# Diff-Probe_Topsheet.net
KiCad netlist of a schematic drawn in Altium Designer
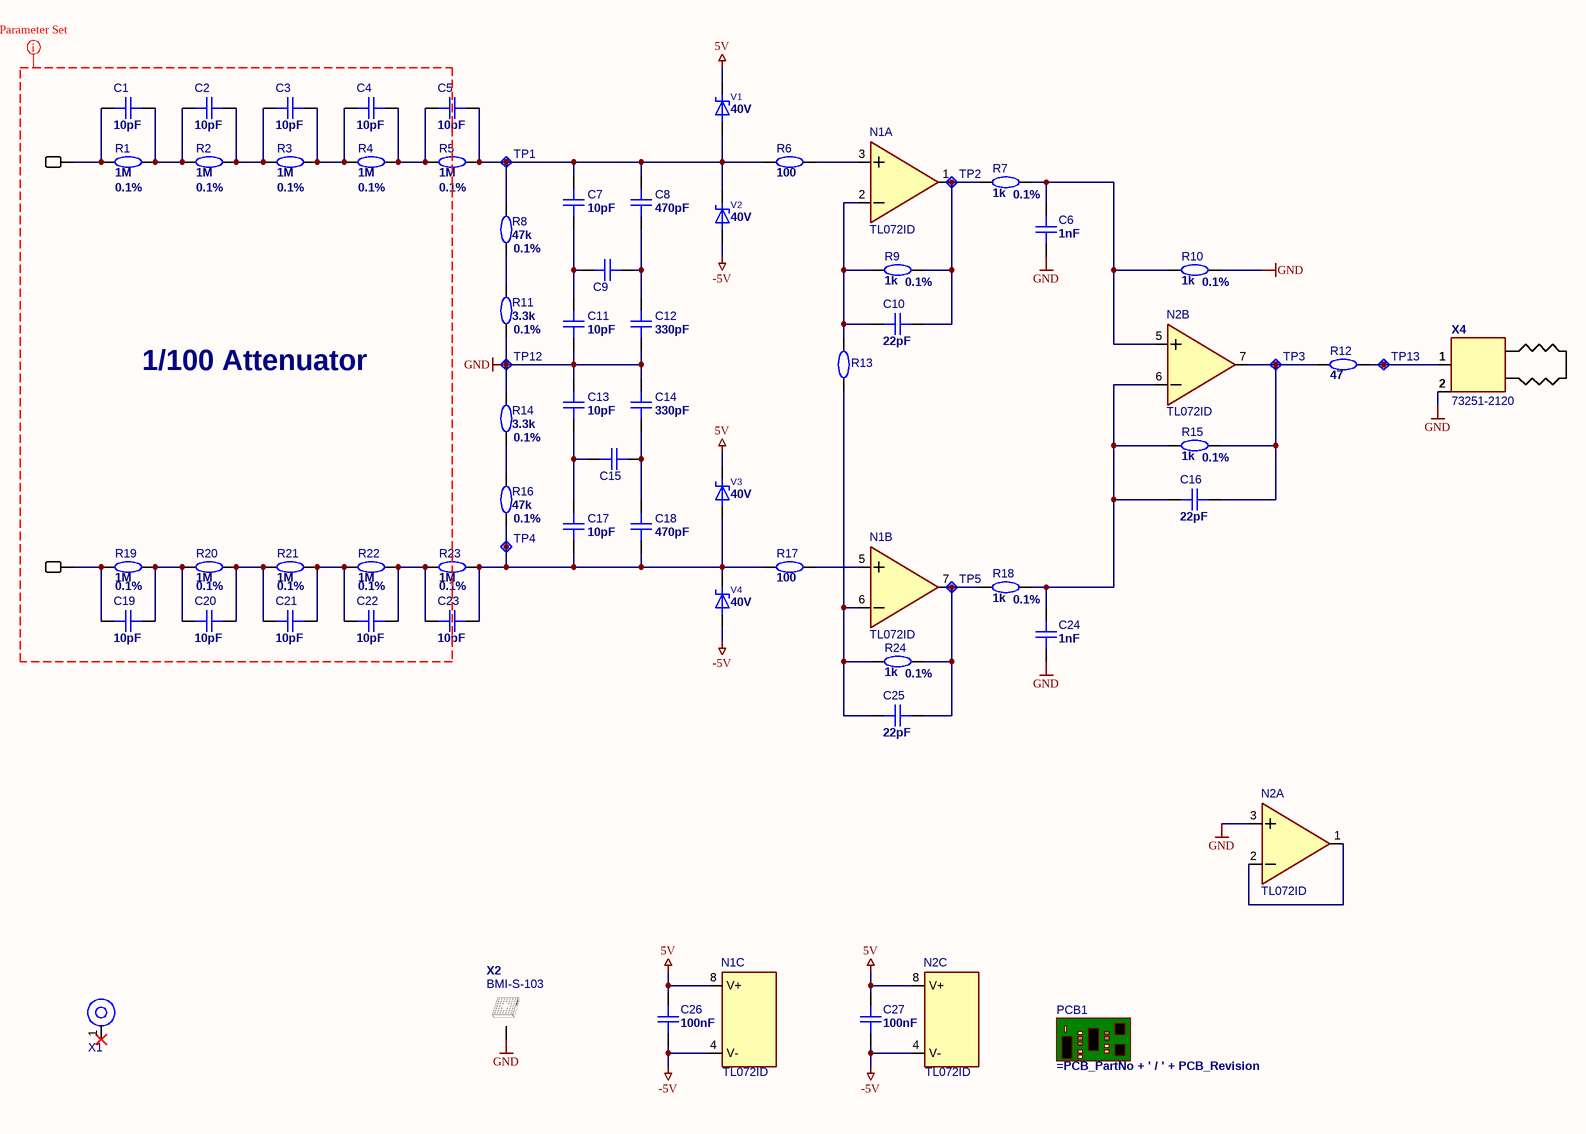
[diagram p0: Diff-Probe_Topsheet.SchDoc]

(export (version "E")
  (design (tool "Eeschema 10.0.6"))
  (components
    (comp (ref "C1")
      (value "10pF")
      (footprint "C-1206_3216_100_L_RF")
      (description "CAP CER 10PF 1KV U2J 1206")
      (fields
        (field (name "PART") "Cap Dummy")
        (field (name "Comment") "CAP 10PF 1KV U2J 1206")
        (field (name "USER") "zupa")
      )
      (libsource (lib "GPV Switzerland SA") (part "CAP"))
    )
    (comp (ref "C2")
      (value "10pF")
      (footprint "C-1206_3216_100_L_RF")
      (description "CAP CER 10PF 1KV U2J 1206")
      (fields
        (field (name "PART") "Cap Dummy")
        (field (name "Comment") "CAP 10PF 1KV U2J 1206")
        (field (name "USER") "zupa")
      )
      (libsource (lib "GPV Switzerland SA") (part "CAP"))
    )
    (comp (ref "C3")
      (value "10pF")
      (footprint "C-1206_3216_100_L_RF")
      (description "CAP CER 10PF 1KV U2J 1206")
      (fields
        (field (name "PART") "Cap Dummy")
        (field (name "Comment") "CAP 10PF 1KV U2J 1206")
        (field (name "USER") "zupa")
      )
      (libsource (lib "GPV Switzerland SA") (part "CAP"))
    )
    (comp (ref "C4")
      (value "10pF")
      (footprint "C-1206_3216_100_L_RF")
      (description "CAP CER 10PF 1KV U2J 1206")
      (fields
        (field (name "PART") "Cap Dummy")
        (field (name "Comment") "CAP 10PF 1KV U2J 1206")
        (field (name "USER") "zupa")
      )
      (libsource (lib "GPV Switzerland SA") (part "CAP"))
    )
    (comp (ref "C5")
      (value "10pF")
      (footprint "C-1206_3216_100_L_RF")
      (description "CAP CER 10PF 1KV U2J 1206")
      (fields
        (field (name "PART") "Cap Dummy")
        (field (name "Comment") "CAP 10PF 1KV U2J 1206")
        (field (name "USER") "zupa")
      )
      (libsource (lib "GPV Switzerland SA") (part "CAP"))
    )
    (comp (ref "C6")
      (value "1nF")
      (footprint "C-0603_1608_100_L_RF")
      (description "Cap Cer SMD 1n 50V 1% 0603 C0G")
      (fields
        (field (name "MANUFACTURER PART NUMBER") "06035A102FAT*")
        (field (name "MANUFACTURER") "AVX")
        (field (name "USER") "zupa")
      )
      (libsource (lib "GPV Switzerland SA") (part "CAP"))
    )
    (comp (ref "C7")
      (value "10pF")
      (footprint "C-0603_1608_095_L_RF")
      (description "Cap Cer SMD 10p 50V +/- 0.25pF  0603 C0G")
      (fields
        (field (name "MANUFACTURER") "AVX")
        (field (name "MANUFACTURER PART NUMBER") "06035A100CAT*")
        (field (name "USER") "zupa")
      )
      (libsource (lib "GPV Switzerland SA") (part "CAP"))
    )
    (comp (ref "C8")
      (value "470pF")
      (footprint "C-0603_1608_095_L_RF")
      (description "Cap Cer SMD 470p 100V 10% 0603 X7R")
      (fields
        (field (name "MANUFACTURER") "AVX")
        (field (name "MANUFACTURER PART NUMBER") "06031C471KAT2A")
        (field (name "USER") "zupa")
      )
      (libsource (lib "GPV Switzerland SA") (part "CAP"))
    )
    (comp (ref "C9")
      (value "Cap 0603")
      (footprint "C-0603_1608_095_L_RF")
      (description "Cap Cer SMD ?n ?V ?% 0603 ?")
      (fields (field (name "MANUFACTURER") "?") (field (name "USER") "zupa"))
      (libsource (lib "GPV Switzerland SA") (part "CAP"))
    )
    (comp (ref "C10")
      (value "22pF")
      (footprint "C-0603_1608_095_L_RF")
      (description "Cap Cer SMD 22p 50V 5% 0603 C0G")
      (fields
        (field (name "MANUFACTURER") "AVX")
        (field (name "MANUFACTURER PART NUMBER") "06035A220JAT")
        (field (name "USER") "zupa")
      )
      (libsource (lib "GPV Switzerland SA") (part "CAP"))
    )
    (comp (ref "C11")
      (value "10pF")
      (footprint "C-0603_1608_095_L_RF")
      (description "Cap Cer SMD 10p 50V +/- 0.25pF  0603 C0G")
      (fields
        (field (name "MANUFACTURER") "AVX")
        (field (name "MANUFACTURER PART NUMBER") "06035A100CAT*")
        (field (name "USER") "zupa")
      )
      (libsource (lib "GPV Switzerland SA") (part "CAP"))
    )
    (comp (ref "C12")
      (value "330pF")
      (footprint "C-0603_1608_095_L_RF")
      (description "Cap Cer SMD 330p 50V 2% 0603 C0G")
      (fields
        (field (name "MANUFACTURER") "MURATA")
        (field (name "MANUFACTURER PART NUMBER") "GRM1885C1H331GA01D")
        (field (name "USER") "zupa")
      )
      (libsource (lib "GPV Switzerland SA") (part "CAP"))
    )
    (comp (ref "C13")
      (value "10pF")
      (footprint "C-0603_1608_095_L_RF")
      (description "Cap Cer SMD 10p 50V +/- 0.25pF  0603 C0G")
      (fields
        (field (name "MANUFACTURER") "AVX")
        (field (name "MANUFACTURER PART NUMBER") "06035A100CAT*")
        (field (name "USER") "zupa")
      )
      (libsource (lib "GPV Switzerland SA") (part "CAP"))
    )
    (comp (ref "C14")
      (value "330pF")
      (footprint "C-0603_1608_095_L_RF")
      (description "Cap Cer SMD 330p 50V 2% 0603 C0G")
      (fields
        (field (name "MANUFACTURER") "MURATA")
        (field (name "MANUFACTURER PART NUMBER") "GRM1885C1H331GA01D")
        (field (name "USER") "zupa")
      )
      (libsource (lib "GPV Switzerland SA") (part "CAP"))
    )
    (comp (ref "C15")
      (value "Cap 0603")
      (footprint "C-0603_1608_095_L_RF")
      (description "Cap Cer SMD ?n ?V ?% 0603 ?")
      (fields (field (name "MANUFACTURER") "?") (field (name "USER") "zupa"))
      (libsource (lib "GPV Switzerland SA") (part "CAP"))
    )
    (comp (ref "C16")
      (value "22pF")
      (footprint "C-0603_1608_095_L_RF")
      (description "Cap Cer SMD 22p 50V 5% 0603 C0G")
      (fields
        (field (name "MANUFACTURER") "AVX")
        (field (name "MANUFACTURER PART NUMBER") "06035A220JAT")
        (field (name "USER") "zupa")
      )
      (libsource (lib "GPV Switzerland SA") (part "CAP"))
    )
    (comp (ref "C17")
      (value "10pF")
      (footprint "C-0603_1608_095_L_RF")
      (description "Cap Cer SMD 10p 50V +/- 0.25pF  0603 C0G")
      (fields
        (field (name "MANUFACTURER") "AVX")
        (field (name "MANUFACTURER PART NUMBER") "06035A100CAT*")
        (field (name "USER") "zupa")
      )
      (libsource (lib "GPV Switzerland SA") (part "CAP"))
    )
    (comp (ref "C18")
      (value "470pF")
      (footprint "C-0603_1608_095_L_RF")
      (description "Cap Cer SMD 470p 100V 10% 0603 X7R")
      (fields
        (field (name "MANUFACTURER") "AVX")
        (field (name "MANUFACTURER PART NUMBER") "06031C471KAT2A")
        (field (name "USER") "zupa")
      )
      (libsource (lib "GPV Switzerland SA") (part "CAP"))
    )
    (comp (ref "C19")
      (value "10pF")
      (footprint "C-1206_3216_100_L_RF")
      (description "CAP CER 10PF 1KV U2J 1206")
      (fields
        (field (name "PART") "Cap Dummy")
        (field (name "Comment") "CAP 10PF 1KV U2J 1206")
        (field (name "USER") "zupa")
      )
      (libsource (lib "GPV Switzerland SA") (part "CAP"))
    )
    (comp (ref "C20")
      (value "10pF")
      (footprint "C-1206_3216_100_L_RF")
      (description "CAP CER 10PF 1KV U2J 1206")
      (fields
        (field (name "PART") "Cap Dummy")
        (field (name "Comment") "CAP 10PF 1KV U2J 1206")
        (field (name "USER") "zupa")
      )
      (libsource (lib "GPV Switzerland SA") (part "CAP"))
    )
    (comp (ref "C21")
      (value "10pF")
      (footprint "C-1206_3216_100_L_RF")
      (description "CAP CER 10PF 1KV U2J 1206")
      (fields
        (field (name "PART") "Cap Dummy")
        (field (name "Comment") "CAP 10PF 1KV U2J 1206")
        (field (name "USER") "zupa")
      )
      (libsource (lib "GPV Switzerland SA") (part "CAP"))
    )
    (comp (ref "C22")
      (value "10pF")
      (footprint "C-1206_3216_100_L_RF")
      (description "CAP CER 10PF 1KV U2J 1206")
      (fields
        (field (name "PART") "Cap Dummy")
        (field (name "Comment") "CAP 10PF 1KV U2J 1206")
        (field (name "USER") "zupa")
      )
      (libsource (lib "GPV Switzerland SA") (part "CAP"))
    )
    (comp (ref "C23")
      (value "10pF")
      (footprint "C-1206_3216_100_L_RF")
      (description "CAP CER 10PF 1KV U2J 1206")
      (fields
        (field (name "PART") "Cap Dummy")
        (field (name "Comment") "CAP 10PF 1KV U2J 1206")
        (field (name "USER") "zupa")
      )
      (libsource (lib "GPV Switzerland SA") (part "CAP"))
    )
    (comp (ref "C24")
      (value "1nF")
      (footprint "C-0603_1608_100_L_RF")
      (description "Cap Cer SMD 1n 50V 1% 0603 C0G")
      (fields
        (field (name "MANUFACTURER PART NUMBER") "06035A102FAT*")
        (field (name "MANUFACTURER") "AVX")
        (field (name "USER") "zupa")
      )
      (libsource (lib "GPV Switzerland SA") (part "CAP"))
    )
    (comp (ref "C25")
      (value "22pF")
      (footprint "C-0603_1608_095_L_RF")
      (description "Cap Cer SMD 22p 50V 5% 0603 C0G")
      (fields
        (field (name "MANUFACTURER") "AVX")
        (field (name "MANUFACTURER PART NUMBER") "06035A220JAT")
        (field (name "USER") "zupa")
      )
      (libsource (lib "GPV Switzerland SA") (part "CAP"))
    )
    (comp (ref "C26")
      (value "100nF")
      (footprint "C-0603_1608_095_L_RF")
      (description "Cap Cer SMD 100n 100V 10% 0603 X7R")
      (fields
        (field (name "MANUFACTURER PART NUMBER") "GRM188R72A104KA35")
        (field (name "MANUFACTURER") "MURATA")
        (field (name "USER") "zupa")
      )
      (libsource (lib "GPV Switzerland SA") (part "CAP"))
    )
    (comp (ref "C27")
      (value "100nF")
      (footprint "C-0603_1608_095_L_RF")
      (description "Cap Cer SMD 100n 100V 10% 0603 X7R")
      (fields
        (field (name "MANUFACTURER PART NUMBER") "GRM188R72A104KA35")
        (field (name "MANUFACTURER") "MURATA")
        (field (name "USER") "zupa")
      )
      (libsource (lib "GPV Switzerland SA") (part "CAP"))
    )
    (comp (ref "N1")
      (value "TL072ID")
      (footprint "SO8_L_RF")
      (description "IC OPAMP JFET 3MHZ 8SOIC")
      (fields
        (field (name "MANUFACTURER") "Texas Instruments")
        (field (name "MANUFACTURER PART NUMBER") "TL072IDR")
        (field (name "USER") "zupa")
      )
      (libsource (lib "GPV Switzerland SA") (part "TL072ID"))
    )
    (comp (ref "N2")
      (value "TL072ID")
      (footprint "SO8_L_RF")
      (description "IC OPAMP JFET 3MHZ 8SOIC")
      (fields
        (field (name "MANUFACTURER") "Texas Instruments")
        (field (name "MANUFACTURER PART NUMBER") "TL072IDR")
        (field (name "USER") "zupa")
      )
      (libsource (lib "GPV Switzerland SA") (part "TL072ID"))
    )
    (comp (ref "PCB1")
      (value "/")
      (footprint "Dummy_PCB-Parameter_SM")
      (description "<PCB DesignName Revision>")
      (fields (field (name "Comment") "PCB_Dummy") (field (name "USER") "balu"))
      (libsource (lib "GPV Switzerland SA") (part "PCB"))
    )
    (comp (ref "R1")
      (value "1M")
      (footprint "R-1206_3216_065_L_RF")
      (description "Res SMD 1M 1% 0.25W 1206")
      (fields
        (field (name "MANUFACTURER PART NUMBER") "RC1206FR-071ML")
        (field (name "MANUFACTURER") "YAGEO")
        (field (name "USER") "zupa")
      )
      (libsource (lib "GPV Switzerland SA") (part "RES"))
    )
    (comp (ref "R2")
      (value "1M")
      (footprint "R-1206_3216_065_L_RF")
      (description "Res SMD 1M 1% 0.25W 1206")
      (fields
        (field (name "MANUFACTURER PART NUMBER") "RC1206FR-071ML")
        (field (name "MANUFACTURER") "YAGEO")
        (field (name "USER") "zupa")
      )
      (libsource (lib "GPV Switzerland SA") (part "RES"))
    )
    (comp (ref "R3")
      (value "1M")
      (footprint "R-1206_3216_065_L_RF")
      (description "Res SMD 1M 1% 0.25W 1206")
      (fields
        (field (name "MANUFACTURER PART NUMBER") "RC1206FR-071ML")
        (field (name "MANUFACTURER") "YAGEO")
        (field (name "USER") "zupa")
      )
      (libsource (lib "GPV Switzerland SA") (part "RES"))
    )
    (comp (ref "R4")
      (value "1M")
      (footprint "R-1206_3216_065_L_RF")
      (description "Res SMD 1M 1% 0.25W 1206")
      (fields
        (field (name "MANUFACTURER PART NUMBER") "RC1206FR-071ML")
        (field (name "MANUFACTURER") "YAGEO")
        (field (name "USER") "zupa")
      )
      (libsource (lib "GPV Switzerland SA") (part "RES"))
    )
    (comp (ref "R5")
      (value "1M")
      (footprint "R-1206_3216_065_L_RF")
      (description "Res SMD 1M 1% 0.25W 1206")
      (fields
        (field (name "MANUFACTURER PART NUMBER") "RC1206FR-071ML")
        (field (name "MANUFACTURER") "YAGEO")
        (field (name "USER") "zupa")
      )
      (libsource (lib "GPV Switzerland SA") (part "RES"))
    )
    (comp (ref "R6")
      (value "100")
      (footprint "R-0603_1608_050_L_RF")
      (description "Res SMD 100R 1% 0.1W 0603")
      (fields
        (field (name "MANUFACTURER") "YAGEO")
        (field (name "MANUFACTURER PART NUMBER") "RC0603FR-07100RL")
        (field (name "USER") "zupa")
      )
      (libsource (lib "GPV Switzerland SA") (part "RES"))
    )
    (comp (ref "R7")
      (value "1k")
      (footprint "R-0603_1608_050_L_RF")
      (description "Res SMD 1k 1% 0.1W 0603")
      (fields
        (field (name "MANUFACTURER") "YAGEO")
        (field (name "MANUFACTURER PART NUMBER") "RC0603FR-071KL")
        (field (name "USER") "zupa")
      )
      (libsource (lib "GPV Switzerland SA") (part "RES"))
    )
    (comp (ref "R8")
      (value "47k")
      (footprint "R-0603_1608_050_L_RF")
      (description "Res SMD 47k 1% 0.1W 0603")
      (fields
        (field (name "MANUFACTURER PART NUMBER") "RC0603FR-0747KL")
        (field (name "MANUFACTURER") "YAGEO")
        (field (name "USER") "zupa")
      )
      (libsource (lib "GPV Switzerland SA") (part "RES"))
    )
    (comp (ref "R9")
      (value "1k")
      (footprint "R-0603_1608_050_L_RF")
      (description "Res SMD 1k 1% 0.1W 0603")
      (fields
        (field (name "MANUFACTURER") "YAGEO")
        (field (name "MANUFACTURER PART NUMBER") "RC0603FR-071KL")
        (field (name "USER") "zupa")
      )
      (libsource (lib "GPV Switzerland SA") (part "RES"))
    )
    (comp (ref "R10")
      (value "1k")
      (footprint "R-0603_1608_050_L_RF")
      (description "Res SMD 1k 1% 0.1W 0603")
      (fields
        (field (name "MANUFACTURER") "YAGEO")
        (field (name "MANUFACTURER PART NUMBER") "RC0603FR-071KL")
        (field (name "USER") "zupa")
      )
      (libsource (lib "GPV Switzerland SA") (part "RES"))
    )
    (comp (ref "R11")
      (value "3.3k")
      (footprint "R-0603_1608_050_L_RF")
      (description "Res SMD 3k3 1% 0.1W 0603")
      (fields
        (field (name "MANUFACTURER") "YAGEO")
        (field (name "MANUFACTURER PART NUMBER") "RT0603FRE073K3L")
        (field (name "USER") "napa")
      )
      (libsource (lib "GPV Switzerland SA") (part "RES"))
    )
    (comp (ref "R12")
      (value "47")
      (footprint "R-0603_1608_050_L_RF")
      (description "Res SMD 47R 1% 0.1W 0603")
      (fields
        (field (name "MANUFACTURER PART NUMBER") "RC0603FR-0747RL")
        (field (name "MANUFACTURER") "YAGEO")
        (field (name "USER") "zupa")
      )
      (libsource (lib "GPV Switzerland SA") (part "RES"))
    )
    (comp (ref "R13")
      (value "Res 0603")
      (footprint "R-0603_1608_050_L_RF")
      (description "Res SMD ?R? ?% 0.1W 0603")
      (fields (field (name "MANUFACTURER") "?") (field (name "USER") "zupa"))
      (libsource (lib "GPV Switzerland SA") (part "RES"))
    )
    (comp (ref "R14")
      (value "3.3k")
      (footprint "R-0603_1608_050_L_RF")
      (description "Res SMD 3k3 1% 0.1W 0603")
      (fields
        (field (name "MANUFACTURER") "YAGEO")
        (field (name "MANUFACTURER PART NUMBER") "RT0603FRE073K3L")
        (field (name "USER") "napa")
      )
      (libsource (lib "GPV Switzerland SA") (part "RES"))
    )
    (comp (ref "R15")
      (value "1k")
      (footprint "R-0603_1608_050_L_RF")
      (description "Res SMD 1k 1% 0.1W 0603")
      (fields
        (field (name "MANUFACTURER") "YAGEO")
        (field (name "MANUFACTURER PART NUMBER") "RC0603FR-071KL")
        (field (name "USER") "zupa")
      )
      (libsource (lib "GPV Switzerland SA") (part "RES"))
    )
    (comp (ref "R16")
      (value "47k")
      (footprint "R-0603_1608_050_L_RF")
      (description "Res SMD 47k 1% 0.1W 0603")
      (fields
        (field (name "MANUFACTURER PART NUMBER") "RC0603FR-0747KL")
        (field (name "MANUFACTURER") "YAGEO")
        (field (name "USER") "zupa")
      )
      (libsource (lib "GPV Switzerland SA") (part "RES"))
    )
    (comp (ref "R17")
      (value "100")
      (footprint "R-0603_1608_050_L_RF")
      (description "Res SMD 100R 1% 0.1W 0603")
      (fields
        (field (name "MANUFACTURER") "YAGEO")
        (field (name "MANUFACTURER PART NUMBER") "RC0603FR-07100RL")
        (field (name "USER") "zupa")
      )
      (libsource (lib "GPV Switzerland SA") (part "RES"))
    )
    (comp (ref "R18")
      (value "1k")
      (footprint "R-0603_1608_050_L_RF")
      (description "Res SMD 1k 1% 0.1W 0603")
      (fields
        (field (name "MANUFACTURER") "YAGEO")
        (field (name "MANUFACTURER PART NUMBER") "RC0603FR-071KL")
        (field (name "USER") "zupa")
      )
      (libsource (lib "GPV Switzerland SA") (part "RES"))
    )
    (comp (ref "R19")
      (value "1M")
      (footprint "R-1206_3216_065_L_RF")
      (description "Res SMD 1M 1% 0.25W 1206")
      (fields
        (field (name "MANUFACTURER PART NUMBER") "RC1206FR-071ML")
        (field (name "MANUFACTURER") "YAGEO")
        (field (name "USER") "zupa")
      )
      (libsource (lib "GPV Switzerland SA") (part "RES"))
    )
    (comp (ref "R20")
      (value "1M")
      (footprint "R-1206_3216_065_L_RF")
      (description "Res SMD 1M 1% 0.25W 1206")
      (fields
        (field (name "MANUFACTURER PART NUMBER") "RC1206FR-071ML")
        (field (name "MANUFACTURER") "YAGEO")
        (field (name "USER") "zupa")
      )
      (libsource (lib "GPV Switzerland SA") (part "RES"))
    )
    (comp (ref "R21")
      (value "1M")
      (footprint "R-1206_3216_065_L_RF")
      (description "Res SMD 1M 1% 0.25W 1206")
      (fields
        (field (name "MANUFACTURER PART NUMBER") "RC1206FR-071ML")
        (field (name "MANUFACTURER") "YAGEO")
        (field (name "USER") "zupa")
      )
      (libsource (lib "GPV Switzerland SA") (part "RES"))
    )
    (comp (ref "R22")
      (value "1M")
      (footprint "R-1206_3216_065_L_RF")
      (description "Res SMD 1M 1% 0.25W 1206")
      (fields
        (field (name "MANUFACTURER PART NUMBER") "RC1206FR-071ML")
        (field (name "MANUFACTURER") "YAGEO")
        (field (name "USER") "zupa")
      )
      (libsource (lib "GPV Switzerland SA") (part "RES"))
    )
    (comp (ref "R23")
      (value "1M")
      (footprint "R-1206_3216_065_L_RF")
      (description "Res SMD 1M 1% 0.25W 1206")
      (fields
        (field (name "MANUFACTURER PART NUMBER") "RC1206FR-071ML")
        (field (name "MANUFACTURER") "YAGEO")
        (field (name "USER") "zupa")
      )
      (libsource (lib "GPV Switzerland SA") (part "RES"))
    )
    (comp (ref "R24")
      (value "1k")
      (footprint "R-0603_1608_050_L_RF")
      (description "Res SMD 1k 1% 0.1W 0603")
      (fields
        (field (name "MANUFACTURER") "YAGEO")
        (field (name "MANUFACTURER PART NUMBER") "RC0603FR-071KL")
        (field (name "USER") "zupa")
      )
      (libsource (lib "GPV Switzerland SA") (part "RES"))
    )
    (comp (ref "R30")
      (value "~")
      (footprint "Lötpad_2x3")
      (description "Solderpad 2mm x 3mm")
      (libsource (lib "Global Library") (part "Lötpad_2mmx3mm"))
    )
    (comp (ref "R31")
      (value "~")
      (footprint "Lötpad_2x3")
      (description "Solderpad 2mm x 3mm")
      (libsource (lib "Global Library") (part "Lötpad_2mmx3mm"))
    )
    (comp (ref "TP1")
      (value "TestPoint 1.6mm with via")
      (footprint "TP_1.6mm_via")
      (description "TestPoint 1.6mm with via v70h30")
      (fields (field (name "USER") "epph"))
      (libsource (lib "GPV Switzerland SA") (part "Testpoint"))
    )
    (comp (ref "TP2")
      (value "TestPoint 1.6mm with via")
      (footprint "TP_1.6mm_via")
      (description "TestPoint 1.6mm with via v70h30")
      (fields (field (name "USER") "epph"))
      (libsource (lib "GPV Switzerland SA") (part "Testpoint"))
    )
    (comp (ref "TP3")
      (value "TestPoint 1.6mm with via")
      (footprint "TP_1.6mm_via")
      (description "TestPoint 1.6mm with via v70h30")
      (fields (field (name "USER") "epph"))
      (libsource (lib "GPV Switzerland SA") (part "Testpoint"))
    )
    (comp (ref "TP4")
      (value "TestPoint 1.6mm with via")
      (footprint "TP_1.6mm_via")
      (description "TestPoint 1.6mm with via v70h30")
      (fields (field (name "USER") "epph"))
      (libsource (lib "GPV Switzerland SA") (part "Testpoint"))
    )
    (comp (ref "TP5")
      (value "TestPoint 1.6mm with via")
      (footprint "TP_1.6mm_via")
      (description "TestPoint 1.6mm with via v70h30")
      (fields (field (name "USER") "epph"))
      (libsource (lib "GPV Switzerland SA") (part "Testpoint"))
    )
    (comp (ref "TP12")
      (value "TestPoint 1.6mm with via")
      (footprint "TP_1.6mm_via")
      (description "TestPoint 1.6mm with via v70h30")
      (fields (field (name "USER") "epph"))
      (libsource (lib "GPV Switzerland SA") (part "Testpoint"))
    )
    (comp (ref "TP13")
      (value "TestPoint 1.6mm with via")
      (footprint "TP_1.6mm_via")
      (description "TestPoint 1.6mm with via v70h30")
      (fields (field (name "USER") "epph"))
      (libsource (lib "GPV Switzerland SA") (part "Testpoint"))
    )
    (comp (ref "V1")
      (value "40V")
      (footprint "SMA_DO214AC_L_RF")
      (description "Diode Schottky 40V 1A SMA")
      (fields
        (field (name "MANUFACTURER") "VISHAY")
        (field (name "MANUFACTURER PART NUMBER") "SS14-E3")
        (field (name "USER") "epph")
      )
      (libsource (lib "GPV Switzerland SA") (part "SCHOTTKY"))
    )
    (comp (ref "V2")
      (value "40V")
      (footprint "SMA_DO214AC_L_RF")
      (description "Diode Schottky 40V 1A SMA")
      (fields
        (field (name "MANUFACTURER") "VISHAY")
        (field (name "MANUFACTURER PART NUMBER") "SS14-E3")
        (field (name "USER") "epph")
      )
      (libsource (lib "GPV Switzerland SA") (part "SCHOTTKY"))
    )
    (comp (ref "V3")
      (value "40V")
      (footprint "SMA_DO214AC_L_RF")
      (description "Diode Schottky 40V 1A SMA")
      (fields
        (field (name "MANUFACTURER") "VISHAY")
        (field (name "MANUFACTURER PART NUMBER") "SS14-E3")
        (field (name "USER") "epph")
      )
      (libsource (lib "GPV Switzerland SA") (part "SCHOTTKY"))
    )
    (comp (ref "V4")
      (value "40V")
      (footprint "SMA_DO214AC_L_RF")
      (description "Diode Schottky 40V 1A SMA")
      (fields
        (field (name "MANUFACTURER") "VISHAY")
        (field (name "MANUFACTURER PART NUMBER") "SS14-E3")
        (field (name "USER") "epph")
      )
      (libsource (lib "GPV Switzerland SA") (part "SCHOTTKY"))
    )
    (comp (ref "X1")
      (value "AnschlussPad_D3.2_P6mm")
      (footprint "A-MountingHole-0600x0600_0320")
      (description "Anschlusspad mit 6mm Pad und 3.2mm Drill")
      (libsource (lib "GPV Switzerland SA") (part "Anschluss-Pad"))
    )
    (comp (ref "X2")
      (value "BMI-S-103")
      (footprint "BMI-S-103")
      (description "EMI Shield 26.2mm x 26.2mm, soldered")
      (fields
        (field (name "MANUFACTURER") "Laird")
        (field (name "PART_VALIDATED") "Yes ¦ No")
        (field (name "FOOTPRINT_VALIDATED") "Yes ¦ No")
      )
      (libsource (lib "Global Library") (part "BMI-S-103"))
    )
    (comp (ref "X4")
      (value "73251-2120")
      (footprint "73251-2120")
      (description "CONN RF SMA")
      (fields (field (name "MANUFACTURER") "MOLEX"))
      (libsource (lib "Global Library") (part "73251-2120"))
    )
  )
  (nets
    (net (code "1") (name "-5V") (class "Default")
      (node (ref "C26") (pin "1") (pinfunction "1_1") (pintype "passive"))
      (node (ref "C27") (pin "1") (pinfunction "1_1") (pintype "passive"))
      (node (ref "N1") (pin "4") (pinfunction "V-_4") (pintype "power_in"))
      (node (ref "N2") (pin "4") (pinfunction "V-_4") (pintype "power_in"))
      (node (ref "V2") (pin "1") (pinfunction "1_1") (pintype "passive"))
      (node (ref "V4") (pin "1") (pinfunction "1_1") (pintype "passive"))
    )
    (net (code "2") (name "5V") (class "Default")
      (node (ref "C26") (pin "2") (pinfunction "2_2") (pintype "passive"))
      (node (ref "C27") (pin "2") (pinfunction "2_2") (pintype "passive"))
      (node (ref "N1") (pin "8") (pinfunction "V+_8") (pintype "power_in"))
      (node (ref "N2") (pin "8") (pinfunction "V+_8") (pintype "power_in"))
      (node (ref "V1") (pin "2") (pinfunction "2_2") (pintype "passive"))
      (node (ref "V3") (pin "2") (pinfunction "2_2") (pintype "passive"))
    )
    (net (code "3") (name "GND") (class "Default")
      (node (ref "C11") (pin "1") (pinfunction "1_1") (pintype "passive"))
      (node (ref "C12") (pin "1") (pinfunction "1_1") (pintype "passive"))
      (node (ref "C13") (pin "2") (pinfunction "2_2") (pintype "passive"))
      (node (ref "C14") (pin "2") (pinfunction "2_2") (pintype "passive"))
      (node (ref "C24") (pin "1") (pinfunction "1_1") (pintype "passive"))
      (node (ref "C6") (pin "1") (pinfunction "1_1") (pintype "passive"))
      (node (ref "N2") (pin "3") (pintype "passive"))
      (node (ref "R10") (pin "2") (pinfunction "2_2") (pintype "passive"))
      (node (ref "R11") (pin "1") (pinfunction "1_1") (pintype "passive"))
      (node (ref "R14") (pin "2") (pinfunction "2_2") (pintype "passive"))
      (node (ref "TP12") (pin "1") (pinfunction "1_1") (pintype "passive"))
      (node (ref "X2") (pin "S") (pintype "passive"))
      (node (ref "X4") (pin "2") (pintype "passive"))
    )
    (net (code "4") (name "Net-(C1-Pad1)") (class "Default")
      (node (ref "C1") (pin "1") (pinfunction "1_1") (pintype "passive"))
      (node (ref "R1") (pin "1") (pinfunction "1_1") (pintype "passive"))
      (node (ref "R30") (pin "1") (pintype "passive"))
    )
    (net (code "5") (name "Net-(C1-Pad2)") (class "Default")
      (node (ref "C1") (pin "2") (pinfunction "2_2") (pintype "passive"))
      (node (ref "C2") (pin "1") (pinfunction "1_1") (pintype "passive"))
      (node (ref "R1") (pin "2") (pinfunction "2_2") (pintype "passive"))
      (node (ref "R2") (pin "1") (pinfunction "1_1") (pintype "passive"))
    )
    (net (code "6") (name "Net-(C2-Pad2)") (class "Default")
      (node (ref "C2") (pin "2") (pinfunction "2_2") (pintype "passive"))
      (node (ref "C3") (pin "1") (pinfunction "1_1") (pintype "passive"))
      (node (ref "R2") (pin "2") (pinfunction "2_2") (pintype "passive"))
      (node (ref "R3") (pin "1") (pinfunction "1_1") (pintype "passive"))
    )
    (net (code "7") (name "Net-(C3-Pad2)") (class "Default")
      (node (ref "C3") (pin "2") (pinfunction "2_2") (pintype "passive"))
      (node (ref "C4") (pin "1") (pinfunction "1_1") (pintype "passive"))
      (node (ref "R3") (pin "2") (pinfunction "2_2") (pintype "passive"))
      (node (ref "R4") (pin "1") (pinfunction "1_1") (pintype "passive"))
    )
    (net (code "8") (name "Net-(C4-Pad2)") (class "Default")
      (node (ref "C4") (pin "2") (pinfunction "2_2") (pintype "passive"))
      (node (ref "C5") (pin "1") (pinfunction "1_1") (pintype "passive"))
      (node (ref "R4") (pin "2") (pinfunction "2_2") (pintype "passive"))
      (node (ref "R5") (pin "1") (pinfunction "1_1") (pintype "passive"))
    )
    (net (code "9") (name "Net-(C5-Pad2)") (class "Default")
      (node (ref "C5") (pin "2") (pinfunction "2_2") (pintype "passive"))
      (node (ref "C7") (pin "2") (pinfunction "2_2") (pintype "passive"))
      (node (ref "C8") (pin "2") (pinfunction "2_2") (pintype "passive"))
      (node (ref "R5") (pin "2") (pinfunction "2_2") (pintype "passive"))
      (node (ref "R6") (pin "1") (pinfunction "1_1") (pintype "passive"))
      (node (ref "R8") (pin "2") (pinfunction "2_2") (pintype "passive"))
      (node (ref "TP1") (pin "1") (pinfunction "1_1") (pintype "passive"))
      (node (ref "V1") (pin "1") (pinfunction "1_1") (pintype "passive"))
      (node (ref "V2") (pin "2") (pinfunction "2_2") (pintype "passive"))
    )
    (net (code "10") (name "Net-(C6-Pad2)") (class "Default")
      (node (ref "C6") (pin "2") (pinfunction "2_2") (pintype "passive"))
      (node (ref "N2") (pin "5") (pintype "passive"))
      (node (ref "R10") (pin "1") (pinfunction "1_1") (pintype "passive"))
      (node (ref "R7") (pin "2") (pinfunction "2_2") (pintype "passive"))
    )
    (net (code "11") (name "Net-(C10-Pad1)") (class "Default")
      (node (ref "C10") (pin "1") (pinfunction "1_1") (pintype "passive"))
      (node (ref "N1") (pin "2") (pintype "passive"))
      (node (ref "R13") (pin "2") (pinfunction "2_2") (pintype "passive"))
      (node (ref "R9") (pin "1") (pinfunction "1_1") (pintype "passive"))
    )
    (net (code "12") (name "Net-(C10-Pad2)") (class "Default")
      (node (ref "C10") (pin "2") (pinfunction "2_2") (pintype "passive"))
      (node (ref "N1") (pin "1") (pintype "passive"))
      (node (ref "R7") (pin "1") (pinfunction "1_1") (pintype "passive"))
      (node (ref "R9") (pin "2") (pinfunction "2_2") (pintype "passive"))
      (node (ref "TP2") (pin "1") (pinfunction "1_1") (pintype "passive"))
    )
    (net (code "13") (name "Net-(C11-Pad2)") (class "Default")
      (node (ref "C11") (pin "2") (pinfunction "2_2") (pintype "passive"))
      (node (ref "C7") (pin "1") (pinfunction "1_1") (pintype "passive"))
      (node (ref "C9") (pin "2") (pinfunction "2_2") (pintype "passive"))
    )
    (net (code "14") (name "Net-(C12-Pad2)") (class "Default")
      (node (ref "C12") (pin "2") (pinfunction "2_2") (pintype "passive"))
      (node (ref "C8") (pin "1") (pinfunction "1_1") (pintype "passive"))
      (node (ref "C9") (pin "1") (pinfunction "1_1") (pintype "passive"))
    )
    (net (code "15") (name "Net-(C13-Pad1)") (class "Default")
      (node (ref "C13") (pin "1") (pinfunction "1_1") (pintype "passive"))
      (node (ref "C15") (pin "2") (pinfunction "2_2") (pintype "passive"))
      (node (ref "C17") (pin "2") (pinfunction "2_2") (pintype "passive"))
    )
    (net (code "16") (name "Net-(C14-Pad1)") (class "Default")
      (node (ref "C14") (pin "1") (pinfunction "1_1") (pintype "passive"))
      (node (ref "C15") (pin "1") (pinfunction "1_1") (pintype "passive"))
      (node (ref "C18") (pin "2") (pinfunction "2_2") (pintype "passive"))
    )
    (net (code "17") (name "Net-(C16-Pad1)") (class "Default")
      (node (ref "C16") (pin "1") (pinfunction "1_1") (pintype "passive"))
      (node (ref "C24") (pin "2") (pinfunction "2_2") (pintype "passive"))
      (node (ref "N2") (pin "6") (pintype "passive"))
      (node (ref "R15") (pin "1") (pinfunction "1_1") (pintype "passive"))
      (node (ref "R18") (pin "2") (pinfunction "2_2") (pintype "passive"))
    )
    (net (code "18") (name "Net-(C16-Pad2)") (class "Default")
      (node (ref "C16") (pin "2") (pinfunction "2_2") (pintype "passive"))
      (node (ref "N2") (pin "7") (pintype "passive"))
      (node (ref "R12") (pin "1") (pinfunction "1_1") (pintype "passive"))
      (node (ref "R15") (pin "2") (pinfunction "2_2") (pintype "passive"))
      (node (ref "TP3") (pin "1") (pinfunction "1_1") (pintype "passive"))
    )
    (net (code "19") (name "Net-(C17-Pad1)") (class "Default")
      (node (ref "C17") (pin "1") (pinfunction "1_1") (pintype "passive"))
      (node (ref "C18") (pin "1") (pinfunction "1_1") (pintype "passive"))
      (node (ref "C23") (pin "2") (pinfunction "2_2") (pintype "passive"))
      (node (ref "R16") (pin "1") (pinfunction "1_1") (pintype "passive"))
      (node (ref "R17") (pin "1") (pinfunction "1_1") (pintype "passive"))
      (node (ref "R23") (pin "2") (pinfunction "2_2") (pintype "passive"))
      (node (ref "TP4") (pin "1") (pinfunction "1_1") (pintype "passive"))
      (node (ref "V3") (pin "1") (pinfunction "1_1") (pintype "passive"))
      (node (ref "V4") (pin "2") (pinfunction "2_2") (pintype "passive"))
    )
    (net (code "20") (name "Net-(C19-Pad1)") (class "Default")
      (node (ref "C19") (pin "1") (pinfunction "1_1") (pintype "passive"))
      (node (ref "R19") (pin "1") (pinfunction "1_1") (pintype "passive"))
      (node (ref "R31") (pin "1") (pintype "passive"))
    )
    (net (code "21") (name "Net-(C19-Pad2)") (class "Default")
      (node (ref "C19") (pin "2") (pinfunction "2_2") (pintype "passive"))
      (node (ref "C20") (pin "1") (pinfunction "1_1") (pintype "passive"))
      (node (ref "R19") (pin "2") (pinfunction "2_2") (pintype "passive"))
      (node (ref "R20") (pin "1") (pinfunction "1_1") (pintype "passive"))
    )
    (net (code "22") (name "Net-(C20-Pad2)") (class "Default")
      (node (ref "C20") (pin "2") (pinfunction "2_2") (pintype "passive"))
      (node (ref "C21") (pin "1") (pinfunction "1_1") (pintype "passive"))
      (node (ref "R20") (pin "2") (pinfunction "2_2") (pintype "passive"))
      (node (ref "R21") (pin "1") (pinfunction "1_1") (pintype "passive"))
    )
    (net (code "23") (name "Net-(C21-Pad2)") (class "Default")
      (node (ref "C21") (pin "2") (pinfunction "2_2") (pintype "passive"))
      (node (ref "C22") (pin "1") (pinfunction "1_1") (pintype "passive"))
      (node (ref "R21") (pin "2") (pinfunction "2_2") (pintype "passive"))
      (node (ref "R22") (pin "1") (pinfunction "1_1") (pintype "passive"))
    )
    (net (code "24") (name "Net-(C22-Pad2)") (class "Default")
      (node (ref "C22") (pin "2") (pinfunction "2_2") (pintype "passive"))
      (node (ref "C23") (pin "1") (pinfunction "1_1") (pintype "passive"))
      (node (ref "R22") (pin "2") (pinfunction "2_2") (pintype "passive"))
      (node (ref "R23") (pin "1") (pinfunction "1_1") (pintype "passive"))
    )
    (net (code "25") (name "Net-(C25-Pad1)") (class "Default")
      (node (ref "C25") (pin "1") (pinfunction "1_1") (pintype "passive"))
      (node (ref "N1") (pin "6") (pintype "passive"))
      (node (ref "R13") (pin "1") (pinfunction "1_1") (pintype "passive"))
      (node (ref "R24") (pin "1") (pinfunction "1_1") (pintype "passive"))
    )
    (net (code "26") (name "Net-(C25-Pad2)") (class "Default")
      (node (ref "C25") (pin "2") (pinfunction "2_2") (pintype "passive"))
      (node (ref "N1") (pin "7") (pintype "passive"))
      (node (ref "R18") (pin "1") (pinfunction "1_1") (pintype "passive"))
      (node (ref "R24") (pin "2") (pinfunction "2_2") (pintype "passive"))
      (node (ref "TP5") (pin "1") (pinfunction "1_1") (pintype "passive"))
    )
    (net (code "27") (name "Net-(N1-Pad3)") (class "Default")
      (node (ref "N1") (pin "3") (pintype "passive"))
      (node (ref "R6") (pin "2") (pinfunction "2_2") (pintype "passive"))
    )
    (net (code "28") (name "Net-(N1-Pad5)") (class "Default")
      (node (ref "N1") (pin "5") (pintype "passive"))
      (node (ref "R17") (pin "2") (pinfunction "2_2") (pintype "passive"))
    )
    (net (code "29") (name "Net-(N2-Pad1)") (class "Default")
      (node (ref "N2") (pin "1") (pintype "passive"))
      (node (ref "N2") (pin "2") (pintype "passive"))
    )
    (net (code "30") (name "Net-(R11-Pad2)") (class "Default")
      (node (ref "R11") (pin "2") (pinfunction "2_2") (pintype "passive"))
      (node (ref "R8") (pin "1") (pinfunction "1_1") (pintype "passive"))
    )
    (net (code "31") (name "Net-(R12-Pad2)") (class "Default")
      (node (ref "R12") (pin "2") (pinfunction "2_2") (pintype "passive"))
      (node (ref "TP13") (pin "1") (pinfunction "1_1") (pintype "passive"))
      (node (ref "X4") (pin "1") (pintype "passive"))
    )
    (net (code "32") (name "Net-(R14-Pad1)") (class "Default")
      (node (ref "R14") (pin "1") (pinfunction "1_1") (pintype "passive"))
      (node (ref "R16") (pin "2") (pinfunction "2_2") (pintype "passive"))
    )
    (net (code "33") (name "unconnected-(X1-Pad1)") (class "Default")
      (node (ref "X1") (pin "1") (pinfunction "1_1") (pintype "passive+no_connect"))
    )
  )
)
